# FPGA_RAM.net
KiCad netlist of a schematic drawn in Altium Designer
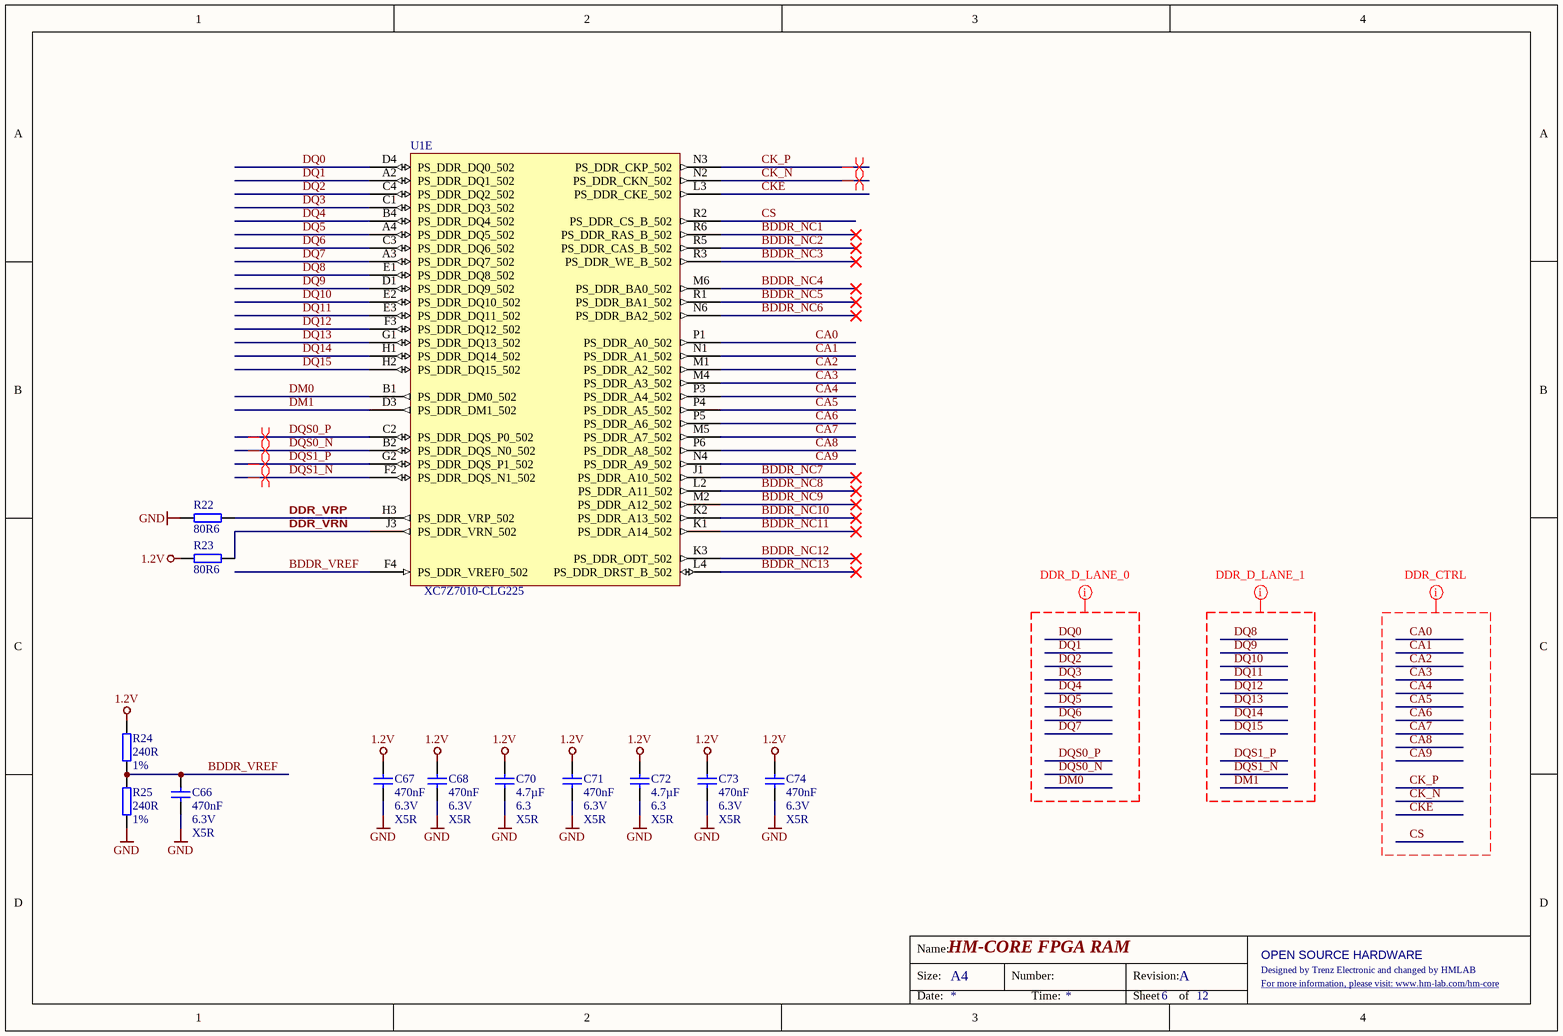
[diagram p0: FPGA_RAM.SchDoc]

(export (version "E")
  (design (tool "Eeschema 10.0.6"))
  (components
    (comp (ref "C66")
      (value "470nF")
      (footprint "CAPC0603X33N")
      (description "KON 470nF X5R 6.3V SMD 20%")
      (fields
        (field (name "VOLTAGE") "6.3V")
        (field (name "TECHNOLOGY") "X5R")
        (field (name "TOLERANCE") "20%")
      )
      (libsource (lib "TE") (part "CAP-NP"))
    )
    (comp (ref "C67")
      (value "470nF")
      (footprint "CAPC0603X33N")
      (description "KON 470nF X5R 6.3V SMD 20%")
      (fields
        (field (name "VOLTAGE") "6.3V")
        (field (name "TECHNOLOGY") "X5R")
        (field (name "TOLERANCE") "20%")
      )
      (libsource (lib "TE") (part "CAP-NP"))
    )
    (comp (ref "C68")
      (value "470nF")
      (footprint "CAPC0603X33N")
      (description "KON 470nF X5R 6.3V SMD 20%")
      (fields
        (field (name "VOLTAGE") "6.3V")
        (field (name "TECHNOLOGY") "X5R")
        (field (name "TOLERANCE") "20%")
      )
      (libsource (lib "TE") (part "CAP-NP"))
    )
    (comp (ref "C70")
      (value "4.7µF")
      (footprint "CAPC1005X60N")
      (description "KON 4.7µF 6.3V X5R SMD 20%")
      (fields
        (field (name "VOLTAGE") "6.3")
        (field (name "TECHNOLOGY") "X5R")
        (field (name "TOLERANCE") "20%")
      )
      (libsource (lib "TE") (part "CAP-NP"))
    )
    (comp (ref "C71")
      (value "470nF")
      (footprint "CAPC0603X33N")
      (description "KON 470nF X5R 6.3V SMD 20%")
      (fields
        (field (name "VOLTAGE") "6.3V")
        (field (name "TECHNOLOGY") "X5R")
        (field (name "TOLERANCE") "20%")
      )
      (libsource (lib "TE") (part "CAP-NP"))
    )
    (comp (ref "C72")
      (value "4.7µF")
      (footprint "CAPC1005X60N")
      (description "KON 4.7µF 6.3V X5R SMD 20%")
      (fields
        (field (name "VOLTAGE") "6.3")
        (field (name "TECHNOLOGY") "X5R")
        (field (name "TOLERANCE") "20%")
      )
      (libsource (lib "TE") (part "CAP-NP"))
    )
    (comp (ref "C73")
      (value "470nF")
      (footprint "CAPC0603X33N")
      (description "KON 470nF X5R 6.3V SMD 20%")
      (fields
        (field (name "VOLTAGE") "6.3V")
        (field (name "TECHNOLOGY") "X5R")
        (field (name "TOLERANCE") "20%")
      )
      (libsource (lib "TE") (part "CAP-NP"))
    )
    (comp (ref "C74")
      (value "470nF")
      (footprint "CAPC0603X33N")
      (description "KON 470nF X5R 6.3V SMD 20%")
      (fields
        (field (name "VOLTAGE") "6.3V")
        (field (name "TECHNOLOGY") "X5R")
        (field (name "TOLERANCE") "20%")
      )
      (libsource (lib "TE") (part "CAP-NP"))
    )
    (comp (ref "R22")
      (value "80R6")
      (footprint "RESC1005X40N")
      (description "WID SMD 80R6 1% 0,063W")
      (fields (field (name "TOLERANCE") "1%"))
      (libsource (lib "TE") (part "RES"))
    )
    (comp (ref "R23")
      (value "80R6")
      (footprint "RESC1005X40N")
      (description "WID SMD 80R6 1% 0,063W")
      (fields (field (name "TOLERANCE") "1%"))
      (libsource (lib "TE") (part "RES"))
    )
    (comp (ref "R24")
      (value "240R")
      (footprint "RESC1005X40N")
      (description "WID SMD 240R 1% 0,063W")
      (fields (field (name "TOLERANCE") "1%"))
      (libsource (lib "TE") (part "RES"))
    )
    (comp (ref "R25")
      (value "240R")
      (footprint "RESC1005X40N")
      (description "WID SMD 240R 1% 0,063W")
      (fields (field (name "TOLERANCE") "1%"))
      (libsource (lib "TE") (part "RES"))
    )
    (comp (ref "U1") (value "XC7Z7010-CLG225") (libsource (lib "XC7Z010-CLG225") (part "XC7Z7010-CLG225")))
  )
  (nets
    (net (code "1") (name "/BDDR_NC1") (class "Default")
      (node (ref "U1") (pin "R6") (pinfunction "PS_DDR_RAS_B_502_R6") (pintype "output+no_connect"))
    )
    (net (code "2") (name "/BDDR_NC2") (class "Default")
      (node (ref "U1") (pin "R5") (pinfunction "PS_DDR_CAS_B_502_R5") (pintype "output+no_connect"))
    )
    (net (code "3") (name "/BDDR_NC3") (class "Default")
      (node (ref "U1") (pin "R3") (pinfunction "PS_DDR_WE_B_502_R3") (pintype "output+no_connect"))
    )
    (net (code "4") (name "/BDDR_NC4") (class "Default")
      (node (ref "U1") (pin "M6") (pinfunction "PS_DDR_BA0_502_M6") (pintype "output+no_connect"))
    )
    (net (code "5") (name "/BDDR_NC5") (class "Default")
      (node (ref "U1") (pin "R1") (pinfunction "PS_DDR_BA1_502_R1") (pintype "output+no_connect"))
    )
    (net (code "6") (name "/BDDR_NC6") (class "Default")
      (node (ref "U1") (pin "N6") (pinfunction "PS_DDR_BA2_502_N6") (pintype "output+no_connect"))
    )
    (net (code "7") (name "/BDDR_NC7") (class "Default")
      (node (ref "U1") (pin "J1") (pinfunction "PS_DDR_A10_502_J1") (pintype "output+no_connect"))
    )
    (net (code "8") (name "/BDDR_NC8") (class "Default")
      (node (ref "U1") (pin "L2") (pinfunction "PS_DDR_A11_502_L2") (pintype "output+no_connect"))
    )
    (net (code "9") (name "/BDDR_NC9") (class "Default")
      (node (ref "U1") (pin "M2") (pinfunction "PS_DDR_A12_502_M2") (pintype "output+no_connect"))
    )
    (net (code "10") (name "/BDDR_NC10") (class "Default")
      (node (ref "U1") (pin "K2") (pinfunction "PS_DDR_A13_502_K2") (pintype "output+no_connect"))
    )
    (net (code "11") (name "/BDDR_NC11") (class "Default")
      (node (ref "U1") (pin "K1") (pinfunction "PS_DDR_A14_502_K1") (pintype "output+no_connect"))
    )
    (net (code "12") (name "/BDDR_NC12") (class "Default")
      (node (ref "U1") (pin "K3") (pinfunction "PS_DDR_ODT_502_K3") (pintype "output+no_connect"))
    )
    (net (code "13") (name "/BDDR_NC13") (class "Default")
      (node (ref "U1") (pin "L4") (pinfunction "PS_DDR_DRST_B_502_L4") (pintype "bidirectional+no_connect"))
    )
    (net (code "14") (name "/BDDR_VREF") (class "Default")
      (node (ref "C66") (pin "1") (pinfunction "1_1") (pintype "passive"))
      (node (ref "R24") (pin "2") (pinfunction "2_2") (pintype "passive"))
      (node (ref "R25") (pin "1") (pinfunction "1_1") (pintype "passive"))
      (node (ref "U1") (pin "F4") (pinfunction "PS_DDR_VREF0_502_F4") (pintype "input"))
    )
    (net (code "15") (name "/CA0") (class "Default")
      (node (ref "U1") (pin "P1") (pinfunction "PS_DDR_A0_502_P1") (pintype "output"))
    )
    (net (code "16") (name "/CA1") (class "Default")
      (node (ref "U1") (pin "N1") (pinfunction "PS_DDR_A1_502_N1") (pintype "output"))
    )
    (net (code "17") (name "/CA2") (class "Default")
      (node (ref "U1") (pin "M1") (pinfunction "PS_DDR_A2_502_M1") (pintype "output"))
    )
    (net (code "18") (name "/CA3") (class "Default")
      (node (ref "U1") (pin "M4") (pinfunction "PS_DDR_A3_502_M4") (pintype "output"))
    )
    (net (code "19") (name "/CA4") (class "Default")
      (node (ref "U1") (pin "P3") (pinfunction "PS_DDR_A4_502_P3") (pintype "output"))
    )
    (net (code "20") (name "/CA5") (class "Default")
      (node (ref "U1") (pin "P4") (pinfunction "PS_DDR_A5_502_P4") (pintype "output"))
    )
    (net (code "21") (name "/CA6") (class "Default")
      (node (ref "U1") (pin "P5") (pinfunction "PS_DDR_A6_502_P5") (pintype "output"))
    )
    (net (code "22") (name "/CA7") (class "Default")
      (node (ref "U1") (pin "M5") (pinfunction "PS_DDR_A7_502_M5") (pintype "output"))
    )
    (net (code "23") (name "/CA8") (class "Default")
      (node (ref "U1") (pin "P6") (pinfunction "PS_DDR_A8_502_P6") (pintype "output"))
    )
    (net (code "24") (name "/CA9") (class "Default")
      (node (ref "U1") (pin "N4") (pinfunction "PS_DDR_A9_502_N4") (pintype "output"))
    )
    (net (code "25") (name "/CKE") (class "Default")
      (node (ref "U1") (pin "L3") (pinfunction "PS_DDR_CKE_502_L3") (pintype "output"))
    )
    (net (code "26") (name "/CK_N") (class "Default")
      (node (ref "U1") (pin "N2") (pinfunction "PS_DDR_CKN_502_N2") (pintype "output"))
    )
    (net (code "27") (name "/CK_P") (class "Default")
      (node (ref "U1") (pin "N3") (pinfunction "PS_DDR_CKP_502_N3") (pintype "output"))
    )
    (net (code "28") (name "/CS") (class "Default")
      (node (ref "U1") (pin "R2") (pinfunction "PS_DDR_CS_B_502_R2") (pintype "output"))
    )
    (net (code "29") (name "/DDR_VRN") (class "Default")
      (node (ref "R23") (pin "2") (pinfunction "2_2") (pintype "passive"))
      (node (ref "U1") (pin "J3") (pinfunction "PS_DDR_VRN_502_J3") (pintype "output"))
    )
    (net (code "30") (name "/DDR_VRP") (class "Default")
      (node (ref "R22") (pin "2") (pinfunction "2_2") (pintype "passive"))
      (node (ref "U1") (pin "H3") (pinfunction "PS_DDR_VRP_502_H3") (pintype "output"))
    )
    (net (code "31") (name "/DM0") (class "Default")
      (node (ref "U1") (pin "B1") (pinfunction "PS_DDR_DM0_502_B1") (pintype "output"))
    )
    (net (code "32") (name "/DM1") (class "Default")
      (node (ref "U1") (pin "D3") (pinfunction "PS_DDR_DM1_502_D3") (pintype "output"))
    )
    (net (code "33") (name "/DQ0") (class "Default")
      (node (ref "U1") (pin "D4") (pinfunction "PS_DDR_DQ0_502_D4") (pintype "bidirectional"))
    )
    (net (code "34") (name "/DQ1") (class "Default")
      (node (ref "U1") (pin "A2") (pinfunction "PS_DDR_DQ1_502_A2") (pintype "bidirectional"))
    )
    (net (code "35") (name "/DQ2") (class "Default")
      (node (ref "U1") (pin "C4") (pinfunction "PS_DDR_DQ2_502_C4") (pintype "bidirectional"))
    )
    (net (code "36") (name "/DQ3") (class "Default")
      (node (ref "U1") (pin "C1") (pinfunction "PS_DDR_DQ3_502_C1") (pintype "bidirectional"))
    )
    (net (code "37") (name "/DQ4") (class "Default")
      (node (ref "U1") (pin "B4") (pinfunction "PS_DDR_DQ4_502_B4") (pintype "bidirectional"))
    )
    (net (code "38") (name "/DQ5") (class "Default")
      (node (ref "U1") (pin "A4") (pinfunction "PS_DDR_DQ5_502_A4") (pintype "bidirectional"))
    )
    (net (code "39") (name "/DQ6") (class "Default")
      (node (ref "U1") (pin "C3") (pinfunction "PS_DDR_DQ6_502_C3") (pintype "bidirectional"))
    )
    (net (code "40") (name "/DQ7") (class "Default")
      (node (ref "U1") (pin "A3") (pinfunction "PS_DDR_DQ7_502_A3") (pintype "bidirectional"))
    )
    (net (code "41") (name "/DQ8") (class "Default")
      (node (ref "U1") (pin "E1") (pinfunction "PS_DDR_DQ8_502_E1") (pintype "bidirectional"))
    )
    (net (code "42") (name "/DQ9") (class "Default")
      (node (ref "U1") (pin "D1") (pinfunction "PS_DDR_DQ9_502_D1") (pintype "bidirectional"))
    )
    (net (code "43") (name "/DQ10") (class "Default")
      (node (ref "U1") (pin "E2") (pinfunction "PS_DDR_DQ10_502_E2") (pintype "bidirectional"))
    )
    (net (code "44") (name "/DQ11") (class "Default")
      (node (ref "U1") (pin "E3") (pinfunction "PS_DDR_DQ11_502_E3") (pintype "bidirectional"))
    )
    (net (code "45") (name "/DQ12") (class "Default")
      (node (ref "U1") (pin "F3") (pinfunction "PS_DDR_DQ12_502_F3") (pintype "bidirectional"))
    )
    (net (code "46") (name "/DQ13") (class "Default")
      (node (ref "U1") (pin "G1") (pinfunction "PS_DDR_DQ13_502_G1") (pintype "bidirectional"))
    )
    (net (code "47") (name "/DQ14") (class "Default")
      (node (ref "U1") (pin "H1") (pinfunction "PS_DDR_DQ14_502_H1") (pintype "bidirectional"))
    )
    (net (code "48") (name "/DQ15") (class "Default")
      (node (ref "U1") (pin "H2") (pinfunction "PS_DDR_DQ15_502_H2") (pintype "bidirectional"))
    )
    (net (code "49") (name "/DQS0_N") (class "Default")
      (node (ref "U1") (pin "B2") (pinfunction "PS_DDR_DQS_N0_502_B2") (pintype "bidirectional"))
    )
    (net (code "50") (name "/DQS0_P") (class "Default")
      (node (ref "U1") (pin "C2") (pinfunction "PS_DDR_DQS_P0_502_C2") (pintype "bidirectional"))
    )
    (net (code "51") (name "/DQS1_N") (class "Default")
      (node (ref "U1") (pin "F2") (pinfunction "PS_DDR_DQS_N1_502_F2") (pintype "bidirectional"))
    )
    (net (code "52") (name "/DQS1_P") (class "Default")
      (node (ref "U1") (pin "G2") (pinfunction "PS_DDR_DQS_P1_502_G2") (pintype "bidirectional"))
    )
    (net (code "53") (name "1.2V") (class "Default")
      (node (ref "C67") (pin "1") (pinfunction "1_1") (pintype "passive"))
      (node (ref "C68") (pin "1") (pinfunction "1_1") (pintype "passive"))
      (node (ref "C70") (pin "1") (pinfunction "1_1") (pintype "passive"))
      (node (ref "C71") (pin "2") (pinfunction "2_2") (pintype "passive"))
      (node (ref "C72") (pin "1") (pinfunction "1_1") (pintype "passive"))
      (node (ref "C73") (pin "2") (pinfunction "2_2") (pintype "passive"))
      (node (ref "C74") (pin "1") (pinfunction "1_1") (pintype "passive"))
      (node (ref "R23") (pin "1") (pinfunction "1_1") (pintype "passive"))
      (node (ref "R24") (pin "1") (pinfunction "1_1") (pintype "passive"))
    )
    (net (code "54") (name "GND") (class "Default")
      (node (ref "C66") (pin "2") (pinfunction "2_2") (pintype "passive"))
      (node (ref "C67") (pin "2") (pinfunction "2_2") (pintype "passive"))
      (node (ref "C68") (pin "2") (pinfunction "2_2") (pintype "passive"))
      (node (ref "C70") (pin "2") (pinfunction "2_2") (pintype "passive"))
      (node (ref "C71") (pin "1") (pinfunction "1_1") (pintype "passive"))
      (node (ref "C72") (pin "2") (pinfunction "2_2") (pintype "passive"))
      (node (ref "C73") (pin "1") (pinfunction "1_1") (pintype "passive"))
      (node (ref "C74") (pin "2") (pinfunction "2_2") (pintype "passive"))
      (node (ref "R22") (pin "1") (pinfunction "1_1") (pintype "passive"))
      (node (ref "R25") (pin "2") (pinfunction "2_2") (pintype "passive"))
    )
  )
)
